# BatteryCharger.net
KiCad netlist of a schematic drawn in Altium Designer
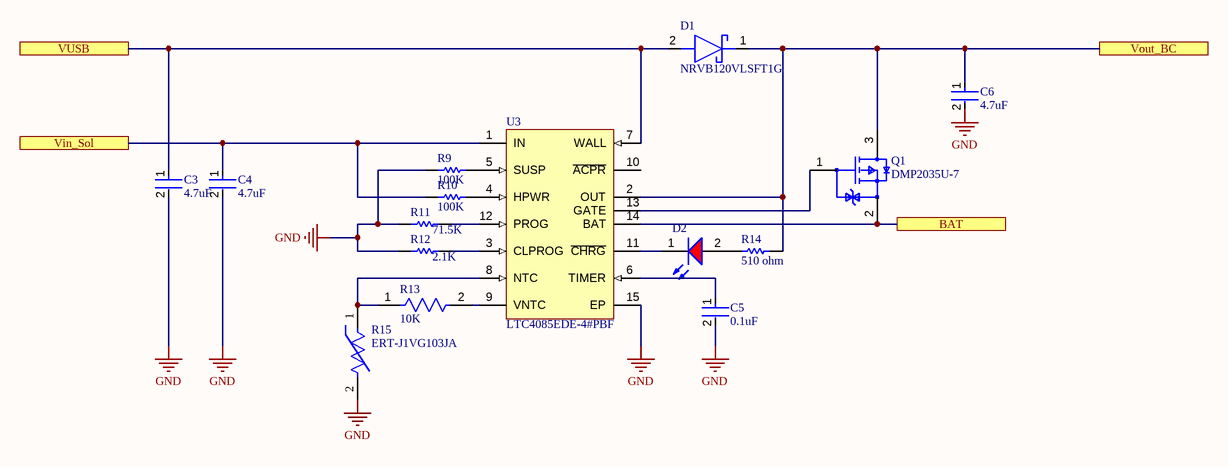
[diagram p0: BatteryCharger.SchDoc]

(export (version "E")
  (design (tool "Eeschema 10.0.6"))
  (components
    (comp (ref "C3")
      (value "4.7uF")
      (footprint "FP-GRM188-0_15-IPC_A")
      (description "CAP CER 4.7UF 10V X7S 0603")
      (fields (field (name "TOLERANCE") "10%"))
      (libsource (lib "Altium Content Vault") (part "02cd4be3c70576c341d710602a673aa"))
    )
    (comp (ref "C4")
      (value "4.7uF")
      (footprint "FP-GRM188-0_15-IPC_A")
      (description "CAP CER 4.7UF 10V X7S 0603")
      (fields (field (name "TOLERANCE") "10%"))
      (libsource (lib "Altium Content Vault") (part "02cd4be3c70576c341d710602a673aa"))
    )
    (comp (ref "C5")
      (value "0.1uF")
      (footprint "FP-C0603C-CF-MFG")
      (description "CAP CER 0.1UF 50V X7R 0603")
      (fields (field (name "TOLERANCE") "0.1") (field (name "MANUFACTURER") "KEMET"))
      (libsource (lib "Altium Content Vault") (part "b4654b650e69147ec39a6b967a45e02"))
    )
    (comp (ref "C6")
      (value "4.7uF")
      (footprint "FP-GRM188-0_15-IPC_A")
      (description "CAP CER 4.7UF 10V X7S 0603")
      (fields (field (name "TOLERANCE") "10%"))
      (libsource (lib "Altium Content Vault") (part "02cd4be3c70576c341d710602a673aa"))
    )
    (comp (ref "D1")
      (value "NRVB120VLSFT1G")
      (footprint "SamacSys:SODFL3616X98N")
      (description "Schottky Diode")
      (fields (field (name "MOUSER PART NUMBER") "863-NRVB120VLSFT1G"))
      (libsource (lib "*") (part "NRVB120VLSFT1G"))
    )
    (comp (ref "D2")
      (value "~")
      (footprint "WL-SMCW_0603_150060xx75000")
      (description "LED Low-Power Uni-Color Red 630nm 2V 2-Pin Chip 0603(1608Metric) T/R")
      (libsource (lib "Altium Content Vault") (part "LED_Red_2A-1K"))
    )
    (comp (ref "Q1")
      (value "DMP2035U-7")
      (footprint "FP-SOT23-IPC_A")
      (description "MOSFET P-CH 20V 3.6A SOT-23")
      (libsource (lib "Altium Content Vault") (part "95361b6375ae2f6c93265ef1e98ed04"))
    )
    (comp (ref "R9")
      (value "100K")
      (footprint "RESC1608X55X30ML20T10")
      (fields (field (name "PART NUMBER") "RK73B1JTTD104J") (field (name "MANUFACTURER") "KOA Speer"))
      (libsource (lib "Altium Content Vault") (part "RES"))
    )
    (comp (ref "R10")
      (value "100K")
      (footprint "RESC1608X55X30ML20T10")
      (fields (field (name "PART NUMBER") "RK73B1JTTD104J") (field (name "MANUFACTURER") "KOA Speer"))
      (libsource (lib "Altium Content Vault") (part "RES"))
    )
    (comp (ref "R11")
      (value "71.5K")
      (footprint "RESC1608X55X30NL15T15")
      (fields (field (name "PART NUMBER") "ERJ-3EKF7152V") (field (name "MANUFACTURER") "Panasonic"))
      (libsource (lib "Altium Content Vault") (part "RES"))
    )
    (comp (ref "R12")
      (value "2.1K")
      (footprint "RESC1608X55X30NL15T15")
      (fields (field (name "PART NUMBER") "ERJ-3EKF2101V") (field (name "MANUFACTURER") "Panasonic"))
      (libsource (lib "Altium Content Vault") (part "RES"))
    )
    (comp (ref "R13")
      (value "10K")
      (footprint "FP-RK73B1J-MFG")
      (description "RES 10K OHM 5% 1/10W 0603")
      (fields (field (name "TOLERANCE") "5%"))
      (libsource (lib "Altium Content Vault") (part "1029c3af85768c4190bb7ad29bc67b5"))
    )
    (comp (ref "R14")
      (value "510 ohm")
      (footprint "RESC1608X55X30ML15T15")
      (fields (field (name "MANUFACTURER") "Panasonic") (field (name "PART NUMBER") "ERJ-3GEYJ511V"))
      (libsource (lib "Altium Content Vault") (part "RES"))
    )
    (comp (ref "R15")
      (value "ERT-J1VG103JA")
      (footprint "FP-ERTJ1-IPC_C")
      (description "THERMISTOR NTC 10KOHM 3380K 0603")
      (fields (field (name "TOLERANCE") "5%"))
      (libsource (lib "Altium Content Vault") (part "3b148a6ebabc5fb4d708a66c052d352"))
    )
    (comp (ref "U3")
      (value "LTC4085EDE-4#PBF")
      (footprint "LT-DE-14_V")
      (fields (field (name "MANUFACTURER") "Linear Technology"))
      (libsource (lib "Altium Content Vault") (part "LT-LTC4085-X-DE-14"))
    )
  )
  (nets
    (net (code "1") (name "/BAT") (class "Default")
      (node (ref "Q1") (pin "2") (pinfunction "S_2") (pintype "passive"))
      (node (ref "U3") (pin "14") (pinfunction "BAT_14") (pintype "power_in"))
    )
    (net (code "2") (name "/VUSB") (class "Default")
      (node (ref "C3") (pin "1") (pinfunction "1_1") (pintype "passive"))
      (node (ref "D1") (pin "2") (pinfunction "A_2") (pintype "passive"))
      (node (ref "U3") (pin "7") (pinfunction "WALL_7") (pintype "input"))
    )
    (net (code "3") (name "/Vin_Sol") (class "Default")
      (node (ref "C4") (pin "1") (pinfunction "1_1") (pintype "passive"))
      (node (ref "R10") (pin "2") (pinfunction "2_2") (pintype "passive"))
      (node (ref "U3") (pin "1") (pinfunction "IN_1") (pintype "power_in"))
    )
    (net (code "4") (name "/Vout_BC") (class "Default")
      (node (ref "C6") (pin "1") (pinfunction "1_1") (pintype "passive"))
      (node (ref "D1") (pin "1") (pinfunction "K_1") (pintype "passive"))
      (node (ref "Q1") (pin "3") (pinfunction "D_3") (pintype "passive"))
      (node (ref "R14") (pin "2") (pinfunction "2_2") (pintype "passive"))
      (node (ref "U3") (pin "2") (pinfunction "OUT_2") (pintype "power_in"))
    )
    (net (code "5") (name "GND") (class "Default")
      (node (ref "C3") (pin "2") (pinfunction "2_2") (pintype "passive"))
      (node (ref "C4") (pin "2") (pinfunction "2_2") (pintype "passive"))
      (node (ref "C5") (pin "2") (pinfunction "2_2") (pintype "passive"))
      (node (ref "C6") (pin "2") (pinfunction "2_2") (pintype "passive"))
      (node (ref "R11") (pin "1") (pinfunction "1_1") (pintype "passive"))
      (node (ref "R12") (pin "1") (pinfunction "1_1") (pintype "passive"))
      (node (ref "R15") (pin "2") (pinfunction "2_2") (pintype "passive"))
      (node (ref "R9") (pin "2") (pinfunction "2_2") (pintype "passive"))
      (node (ref "U3") (pin "15") (pinfunction "EP_15") (pintype "power_in"))
    )
    (net (code "6") (name "Net-(D2-A)") (class "Default")
      (node (ref "D2") (pin "2") (pinfunction "A_2") (pintype "passive"))
      (node (ref "R14") (pin "1") (pinfunction "1_1") (pintype "passive"))
    )
    (net (code "7") (name "Net-(D2-K)") (class "Default")
      (node (ref "D2") (pin "1") (pinfunction "K_1") (pintype "passive"))
      (node (ref "U3") (pin "11") (pinfunction "~{CHRG}_11") (pintype "tri_state"))
    )
    (net (code "8") (name "Net-(Q1-G)") (class "Default")
      (node (ref "Q1") (pin "1") (pinfunction "G_1") (pintype "passive"))
      (node (ref "U3") (pin "13") (pinfunction "GATE_13") (pintype "tri_state"))
    )
    (net (code "9") (name "Net-(U3-CLPROG)") (class "Default")
      (node (ref "R12") (pin "2") (pinfunction "2_2") (pintype "passive"))
      (node (ref "U3") (pin "3") (pinfunction "CLPROG_3") (pintype "input"))
    )
    (net (code "10") (name "Net-(U3-HPWR)") (class "Default")
      (node (ref "R10") (pin "1") (pinfunction "1_1") (pintype "passive"))
      (node (ref "U3") (pin "4") (pinfunction "HPWR_4") (pintype "input"))
    )
    (net (code "11") (name "Net-(U3-NTC)") (class "Default")
      (node (ref "R13") (pin "1") (pinfunction "1_1") (pintype "passive"))
      (node (ref "R15") (pin "1") (pinfunction "1_1") (pintype "passive"))
      (node (ref "U3") (pin "8") (pinfunction "NTC_8") (pintype "input"))
    )
    (net (code "12") (name "Net-(U3-PROG)") (class "Default")
      (node (ref "R11") (pin "2") (pinfunction "2_2") (pintype "passive"))
      (node (ref "U3") (pin "12") (pinfunction "PROG_12") (pintype "input"))
    )
    (net (code "13") (name "Net-(U3-SUSP)") (class "Default")
      (node (ref "R9") (pin "1") (pinfunction "1_1") (pintype "passive"))
      (node (ref "U3") (pin "5") (pinfunction "SUSP_5") (pintype "input"))
    )
    (net (code "14") (name "Net-(U3-TIMER)") (class "Default")
      (node (ref "C5") (pin "1") (pinfunction "1_1") (pintype "passive"))
      (node (ref "U3") (pin "6") (pinfunction "TIMER_6") (pintype "input"))
    )
    (net (code "15") (name "Net-(U3-VNTC)") (class "Default")
      (node (ref "R13") (pin "2") (pinfunction "2_2") (pintype "passive"))
      (node (ref "U3") (pin "9") (pinfunction "VNTC_9") (pintype "passive"))
    )
    (net (code "16") (name "unconnected-(U3-~{ACPR}-Pad10)") (class "Default")
      (node (ref "U3") (pin "10") (pinfunction "~{ACPR}_10") (pintype "tri_state"))
    )
  )
)
